# GALI.net
KiCad netlist of a schematic drawn in EAGLE
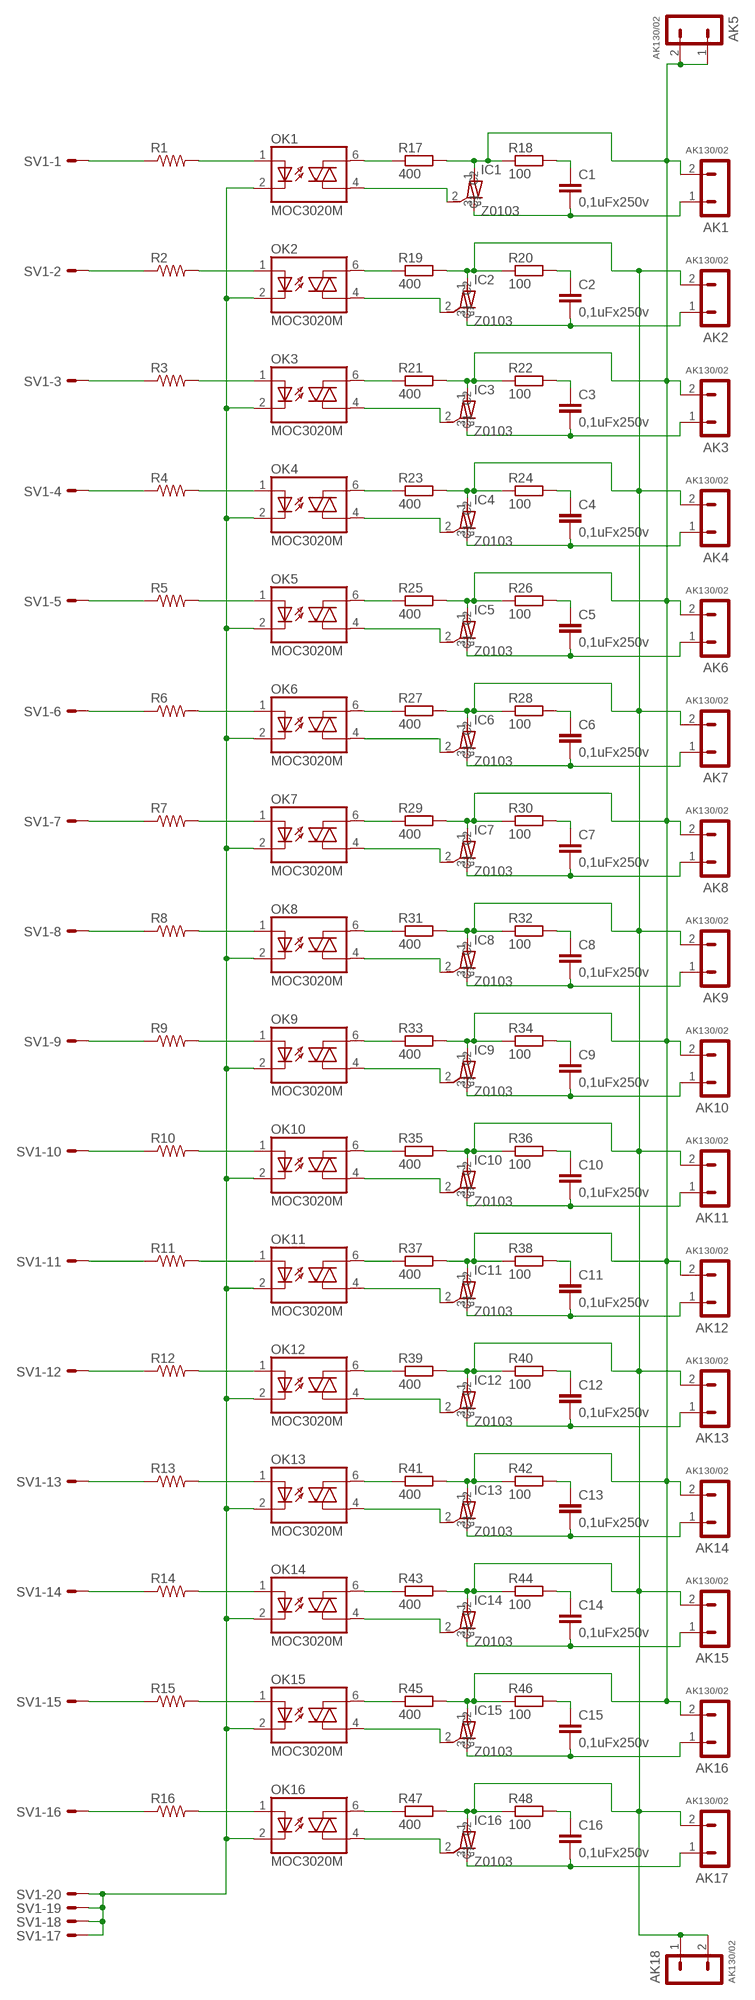
[diagram p0: schematic, sheet 1]

(export (version "E")
  (design (tool "Eeschema 10.0.6"))
  (components
    (comp (ref "AK1")
      (value "AK130/02")
      (footprint "eagle-import:AK02")
      (libsource (lib "eagle-import") (part "AK130/02"))
    )
    (comp (ref "AK2")
      (value "AK130/02")
      (footprint "eagle-import:AK02")
      (libsource (lib "eagle-import") (part "AK130/02"))
    )
    (comp (ref "AK3")
      (value "AK130/02")
      (footprint "eagle-import:AK02")
      (libsource (lib "eagle-import") (part "AK130/02"))
    )
    (comp (ref "AK4")
      (value "AK130/02")
      (footprint "eagle-import:AK02")
      (libsource (lib "eagle-import") (part "AK130/02"))
    )
    (comp (ref "AK5")
      (value "AK130/02")
      (footprint "eagle-import:AK02")
      (libsource (lib "eagle-import") (part "AK130/02"))
    )
    (comp (ref "AK6")
      (value "AK130/02")
      (footprint "eagle-import:AK02")
      (libsource (lib "eagle-import") (part "AK130/02"))
    )
    (comp (ref "AK7")
      (value "AK130/02")
      (footprint "eagle-import:AK02")
      (libsource (lib "eagle-import") (part "AK130/02"))
    )
    (comp (ref "AK8")
      (value "AK130/02")
      (footprint "eagle-import:AK02")
      (libsource (lib "eagle-import") (part "AK130/02"))
    )
    (comp (ref "AK9")
      (value "AK130/02")
      (footprint "eagle-import:AK02")
      (libsource (lib "eagle-import") (part "AK130/02"))
    )
    (comp (ref "AK10")
      (value "AK130/02")
      (footprint "eagle-import:AK02")
      (libsource (lib "eagle-import") (part "AK130/02"))
    )
    (comp (ref "AK11")
      (value "AK130/02")
      (footprint "eagle-import:AK02")
      (libsource (lib "eagle-import") (part "AK130/02"))
    )
    (comp (ref "AK12")
      (value "AK130/02")
      (footprint "eagle-import:AK02")
      (libsource (lib "eagle-import") (part "AK130/02"))
    )
    (comp (ref "AK13")
      (value "AK130/02")
      (footprint "eagle-import:AK02")
      (libsource (lib "eagle-import") (part "AK130/02"))
    )
    (comp (ref "AK14")
      (value "AK130/02")
      (footprint "eagle-import:AK02")
      (libsource (lib "eagle-import") (part "AK130/02"))
    )
    (comp (ref "AK15")
      (value "AK130/02")
      (footprint "eagle-import:AK02")
      (libsource (lib "eagle-import") (part "AK130/02"))
    )
    (comp (ref "AK16")
      (value "AK130/02")
      (footprint "eagle-import:AK02")
      (libsource (lib "eagle-import") (part "AK130/02"))
    )
    (comp (ref "AK17")
      (value "AK130/02")
      (footprint "eagle-import:AK02")
      (libsource (lib "eagle-import") (part "AK130/02"))
    )
    (comp (ref "AK18")
      (value "AK130/02")
      (footprint "eagle-import:AK02")
      (libsource (lib "eagle-import") (part "AK130/02"))
    )
    (comp (ref "C1")
      (value "0,1uFx250v")
      (footprint "eagle-import:C102-054X133")
      (libsource (lib "eagle-import") (part "C-EU102-054X133"))
    )
    (comp (ref "C2")
      (value "0,1uFx250v")
      (footprint "eagle-import:C102-054X133")
      (libsource (lib "eagle-import") (part "C-EU102-054X133"))
    )
    (comp (ref "C3")
      (value "0,1uFx250v")
      (footprint "eagle-import:C102-054X133")
      (libsource (lib "eagle-import") (part "C-EU102-054X133"))
    )
    (comp (ref "C4")
      (value "0,1uFx250v")
      (footprint "eagle-import:C102-054X133")
      (libsource (lib "eagle-import") (part "C-EU102-054X133"))
    )
    (comp (ref "C5")
      (value "0,1uFx250v")
      (footprint "eagle-import:C102-054X133")
      (libsource (lib "eagle-import") (part "C-EU102-054X133"))
    )
    (comp (ref "C6")
      (value "0,1uFx250v")
      (footprint "eagle-import:C102-054X133")
      (libsource (lib "eagle-import") (part "C-EU102-054X133"))
    )
    (comp (ref "C7")
      (value "0,1uFx250v")
      (footprint "eagle-import:C102-054X133")
      (libsource (lib "eagle-import") (part "C-EU102-054X133"))
    )
    (comp (ref "C8")
      (value "0,1uFx250v")
      (footprint "eagle-import:C102-054X133")
      (libsource (lib "eagle-import") (part "C-EU102-054X133"))
    )
    (comp (ref "C9")
      (value "0,1uFx250v")
      (footprint "eagle-import:C102-054X133")
      (libsource (lib "eagle-import") (part "C-EU102-054X133"))
    )
    (comp (ref "C10")
      (value "0,1uFx250v")
      (footprint "eagle-import:C102-054X133")
      (libsource (lib "eagle-import") (part "C-EU102-054X133"))
    )
    (comp (ref "C11")
      (value "0,1uFx250v")
      (footprint "eagle-import:C102-054X133")
      (libsource (lib "eagle-import") (part "C-EU102-054X133"))
    )
    (comp (ref "C12")
      (value "0,1uFx250v")
      (footprint "eagle-import:C102-054X133")
      (libsource (lib "eagle-import") (part "C-EU102-054X133"))
    )
    (comp (ref "C13")
      (value "0,1uFx250v")
      (footprint "eagle-import:C102-054X133")
      (libsource (lib "eagle-import") (part "C-EU102-054X133"))
    )
    (comp (ref "C14")
      (value "0,1uFx250v")
      (footprint "eagle-import:C102-054X133")
      (libsource (lib "eagle-import") (part "C-EU102-054X133"))
    )
    (comp (ref "C15")
      (value "0,1uFx250v")
      (footprint "eagle-import:C102-054X133")
      (libsource (lib "eagle-import") (part "C-EU102-054X133"))
    )
    (comp (ref "C16")
      (value "0,1uFx250v")
      (footprint "eagle-import:C102-054X133")
      (libsource (lib "eagle-import") (part "C-EU102-054X133"))
    )
    (comp (ref "IC1")
      (value "Z0103")
      (footprint "eagle-import:TO92-")
      (libsource (lib "eagle-import") (part "Z0103"))
    )
    (comp (ref "IC2")
      (value "Z0103")
      (footprint "eagle-import:TO92-")
      (libsource (lib "eagle-import") (part "Z0103"))
    )
    (comp (ref "IC3")
      (value "Z0103")
      (footprint "eagle-import:TO92-")
      (libsource (lib "eagle-import") (part "Z0103"))
    )
    (comp (ref "IC4")
      (value "Z0103")
      (footprint "eagle-import:TO92-")
      (libsource (lib "eagle-import") (part "Z0103"))
    )
    (comp (ref "IC5")
      (value "Z0103")
      (footprint "eagle-import:TO92-")
      (libsource (lib "eagle-import") (part "Z0103"))
    )
    (comp (ref "IC6")
      (value "Z0103")
      (footprint "eagle-import:TO92-")
      (libsource (lib "eagle-import") (part "Z0103"))
    )
    (comp (ref "IC7")
      (value "Z0103")
      (footprint "eagle-import:TO92-")
      (libsource (lib "eagle-import") (part "Z0103"))
    )
    (comp (ref "IC8")
      (value "Z0103")
      (footprint "eagle-import:TO92-")
      (libsource (lib "eagle-import") (part "Z0103"))
    )
    (comp (ref "IC9")
      (value "Z0103")
      (footprint "eagle-import:TO92-")
      (libsource (lib "eagle-import") (part "Z0103"))
    )
    (comp (ref "IC10")
      (value "Z0103")
      (footprint "eagle-import:TO92-")
      (libsource (lib "eagle-import") (part "Z0103"))
    )
    (comp (ref "IC11")
      (value "Z0103")
      (footprint "eagle-import:TO92-")
      (libsource (lib "eagle-import") (part "Z0103"))
    )
    (comp (ref "IC12")
      (value "Z0103")
      (footprint "eagle-import:TO92-")
      (libsource (lib "eagle-import") (part "Z0103"))
    )
    (comp (ref "IC13")
      (value "Z0103")
      (footprint "eagle-import:TO92-")
      (libsource (lib "eagle-import") (part "Z0103"))
    )
    (comp (ref "IC14")
      (value "Z0103")
      (footprint "eagle-import:TO92-")
      (libsource (lib "eagle-import") (part "Z0103"))
    )
    (comp (ref "IC15")
      (value "Z0103")
      (footprint "eagle-import:TO92-")
      (libsource (lib "eagle-import") (part "Z0103"))
    )
    (comp (ref "IC16")
      (value "Z0103")
      (footprint "eagle-import:TO92-")
      (libsource (lib "eagle-import") (part "Z0103"))
    )
    (comp (ref "OK1")
      (value "MOC3020M")
      (footprint "eagle-import:DIL06")
      (libsource (lib "eagle-import") (part "MOC30M20"))
    )
    (comp (ref "OK2")
      (value "MOC3020M")
      (footprint "eagle-import:DIL06")
      (libsource (lib "eagle-import") (part "MOC30M20"))
    )
    (comp (ref "OK3")
      (value "MOC3020M")
      (footprint "eagle-import:DIL06")
      (libsource (lib "eagle-import") (part "MOC30M20"))
    )
    (comp (ref "OK4")
      (value "MOC3020M")
      (footprint "eagle-import:DIL06")
      (libsource (lib "eagle-import") (part "MOC30M20"))
    )
    (comp (ref "OK5")
      (value "MOC3020M")
      (footprint "eagle-import:DIL06")
      (libsource (lib "eagle-import") (part "MOC30M20"))
    )
    (comp (ref "OK6")
      (value "MOC3020M")
      (footprint "eagle-import:DIL06")
      (libsource (lib "eagle-import") (part "MOC30M20"))
    )
    (comp (ref "OK7")
      (value "MOC3020M")
      (footprint "eagle-import:DIL06")
      (libsource (lib "eagle-import") (part "MOC30M20"))
    )
    (comp (ref "OK8")
      (value "MOC3020M")
      (footprint "eagle-import:DIL06")
      (libsource (lib "eagle-import") (part "MOC30M20"))
    )
    (comp (ref "OK9")
      (value "MOC3020M")
      (footprint "eagle-import:DIL06")
      (libsource (lib "eagle-import") (part "MOC30M20"))
    )
    (comp (ref "OK10")
      (value "MOC3020M")
      (footprint "eagle-import:DIL06")
      (libsource (lib "eagle-import") (part "MOC30M20"))
    )
    (comp (ref "OK11")
      (value "MOC3020M")
      (footprint "eagle-import:DIL06")
      (libsource (lib "eagle-import") (part "MOC30M20"))
    )
    (comp (ref "OK12")
      (value "MOC3020M")
      (footprint "eagle-import:DIL06")
      (libsource (lib "eagle-import") (part "MOC30M20"))
    )
    (comp (ref "OK13")
      (value "MOC3020M")
      (footprint "eagle-import:DIL06")
      (libsource (lib "eagle-import") (part "MOC30M20"))
    )
    (comp (ref "OK14")
      (value "MOC3020M")
      (footprint "eagle-import:DIL06")
      (libsource (lib "eagle-import") (part "MOC30M20"))
    )
    (comp (ref "OK15")
      (value "MOC3020M")
      (footprint "eagle-import:DIL06")
      (libsource (lib "eagle-import") (part "MOC30M20"))
    )
    (comp (ref "OK16")
      (value "MOC3020M")
      (footprint "eagle-import:DIL06")
      (libsource (lib "eagle-import") (part "MOC30M20"))
    )
    (comp (ref "R1")
      (value "R-US_0207/12")
      (footprint "eagle-import:0207_12")
      (libsource (lib "eagle-import") (part "R-US_0207/12"))
    )
    (comp (ref "R2")
      (value "R-US_0207/12")
      (footprint "eagle-import:0207_12")
      (libsource (lib "eagle-import") (part "R-US_0207/12"))
    )
    (comp (ref "R3")
      (value "R-US_0207/12")
      (footprint "eagle-import:0207_12")
      (libsource (lib "eagle-import") (part "R-US_0207/12"))
    )
    (comp (ref "R4")
      (value "R-US_0207/12")
      (footprint "eagle-import:0207_12")
      (libsource (lib "eagle-import") (part "R-US_0207/12"))
    )
    (comp (ref "R5")
      (value "R-US_0207/12")
      (footprint "eagle-import:0207_12")
      (libsource (lib "eagle-import") (part "R-US_0207/12"))
    )
    (comp (ref "R6")
      (value "R-US_0207/12")
      (footprint "eagle-import:0207_12")
      (libsource (lib "eagle-import") (part "R-US_0207/12"))
    )
    (comp (ref "R7")
      (value "R-US_0207/12")
      (footprint "eagle-import:0207_12")
      (libsource (lib "eagle-import") (part "R-US_0207/12"))
    )
    (comp (ref "R8")
      (value "R-US_0207/12")
      (footprint "eagle-import:0207_12")
      (libsource (lib "eagle-import") (part "R-US_0207/12"))
    )
    (comp (ref "R9")
      (value "R-US_0207/12")
      (footprint "eagle-import:0207_12")
      (libsource (lib "eagle-import") (part "R-US_0207/12"))
    )
    (comp (ref "R10")
      (value "R-US_0207/12")
      (footprint "eagle-import:0207_12")
      (libsource (lib "eagle-import") (part "R-US_0207/12"))
    )
    (comp (ref "R11")
      (value "R-US_0207/12")
      (footprint "eagle-import:0207_12")
      (libsource (lib "eagle-import") (part "R-US_0207/12"))
    )
    (comp (ref "R12")
      (value "R-US_0207/12")
      (footprint "eagle-import:0207_12")
      (libsource (lib "eagle-import") (part "R-US_0207/12"))
    )
    (comp (ref "R13")
      (value "R-US_0207/12")
      (footprint "eagle-import:0207_12")
      (libsource (lib "eagle-import") (part "R-US_0207/12"))
    )
    (comp (ref "R14")
      (value "R-US_0207/12")
      (footprint "eagle-import:0207_12")
      (libsource (lib "eagle-import") (part "R-US_0207/12"))
    )
    (comp (ref "R15")
      (value "R-US_0207/12")
      (footprint "eagle-import:0207_12")
      (libsource (lib "eagle-import") (part "R-US_0207/12"))
    )
    (comp (ref "R16")
      (value "R-US_0207/12")
      (footprint "eagle-import:0207_12")
      (libsource (lib "eagle-import") (part "R-US_0207/12"))
    )
    (comp (ref "R17")
      (value "400")
      (footprint "eagle-import:P0613_15")
      (libsource (lib "eagle-import") (part "R-EU_0613/15"))
    )
    (comp (ref "R18")
      (value "100")
      (footprint "eagle-import:P0613_15")
      (libsource (lib "eagle-import") (part "R-EU_0613/15"))
    )
    (comp (ref "R19")
      (value "400")
      (footprint "eagle-import:P0613_15")
      (libsource (lib "eagle-import") (part "R-EU_0613/15"))
    )
    (comp (ref "R20")
      (value "100")
      (footprint "eagle-import:P0613_15")
      (libsource (lib "eagle-import") (part "R-EU_0613/15"))
    )
    (comp (ref "R21")
      (value "400")
      (footprint "eagle-import:P0613_15")
      (libsource (lib "eagle-import") (part "R-EU_0613/15"))
    )
    (comp (ref "R22")
      (value "100")
      (footprint "eagle-import:P0613_15")
      (libsource (lib "eagle-import") (part "R-EU_0613/15"))
    )
    (comp (ref "R23")
      (value "400")
      (footprint "eagle-import:P0613_15")
      (libsource (lib "eagle-import") (part "R-EU_0613/15"))
    )
    (comp (ref "R24")
      (value "100")
      (footprint "eagle-import:P0613_15")
      (libsource (lib "eagle-import") (part "R-EU_0613/15"))
    )
    (comp (ref "R25")
      (value "400")
      (footprint "eagle-import:P0613_15")
      (libsource (lib "eagle-import") (part "R-EU_0613/15"))
    )
    (comp (ref "R26")
      (value "100")
      (footprint "eagle-import:P0613_15")
      (libsource (lib "eagle-import") (part "R-EU_0613/15"))
    )
    (comp (ref "R27")
      (value "400")
      (footprint "eagle-import:P0613_15")
      (libsource (lib "eagle-import") (part "R-EU_0613/15"))
    )
    (comp (ref "R28")
      (value "100")
      (footprint "eagle-import:P0613_15")
      (libsource (lib "eagle-import") (part "R-EU_0613/15"))
    )
    (comp (ref "R29")
      (value "400")
      (footprint "eagle-import:P0613_15")
      (libsource (lib "eagle-import") (part "R-EU_0613/15"))
    )
    (comp (ref "R30")
      (value "100")
      (footprint "eagle-import:P0613_15")
      (libsource (lib "eagle-import") (part "R-EU_0613/15"))
    )
    (comp (ref "R31")
      (value "400")
      (footprint "eagle-import:P0613_15")
      (libsource (lib "eagle-import") (part "R-EU_0613/15"))
    )
    (comp (ref "R32")
      (value "100")
      (footprint "eagle-import:P0613_15")
      (libsource (lib "eagle-import") (part "R-EU_0613/15"))
    )
    (comp (ref "R33")
      (value "400")
      (footprint "eagle-import:P0613_15")
      (libsource (lib "eagle-import") (part "R-EU_0613/15"))
    )
    (comp (ref "R34")
      (value "100")
      (footprint "eagle-import:P0613_15")
      (libsource (lib "eagle-import") (part "R-EU_0613/15"))
    )
    (comp (ref "R35")
      (value "400")
      (footprint "eagle-import:P0613_15")
      (libsource (lib "eagle-import") (part "R-EU_0613/15"))
    )
    (comp (ref "R36")
      (value "100")
      (footprint "eagle-import:P0613_15")
      (libsource (lib "eagle-import") (part "R-EU_0613/15"))
    )
    (comp (ref "R37")
      (value "400")
      (footprint "eagle-import:P0613_15")
      (libsource (lib "eagle-import") (part "R-EU_0613/15"))
    )
    (comp (ref "R38")
      (value "100")
      (footprint "eagle-import:P0613_15")
      (libsource (lib "eagle-import") (part "R-EU_0613/15"))
    )
    (comp (ref "R39")
      (value "400")
      (footprint "eagle-import:P0613_15")
      (libsource (lib "eagle-import") (part "R-EU_0613/15"))
    )
    (comp (ref "R40")
      (value "100")
      (footprint "eagle-import:P0613_15")
      (libsource (lib "eagle-import") (part "R-EU_0613/15"))
    )
    (comp (ref "R41")
      (value "400")
      (footprint "eagle-import:P0613_15")
      (libsource (lib "eagle-import") (part "R-EU_0613/15"))
    )
    (comp (ref "R42")
      (value "100")
      (footprint "eagle-import:P0613_15")
      (libsource (lib "eagle-import") (part "R-EU_0613/15"))
    )
    (comp (ref "R43")
      (value "400")
      (footprint "eagle-import:P0613_15")
      (libsource (lib "eagle-import") (part "R-EU_0613/15"))
    )
    (comp (ref "R44")
      (value "100")
      (footprint "eagle-import:P0613_15")
      (libsource (lib "eagle-import") (part "R-EU_0613/15"))
    )
    (comp (ref "R45")
      (value "400")
      (footprint "eagle-import:P0613_15")
      (libsource (lib "eagle-import") (part "R-EU_0613/15"))
    )
    (comp (ref "R46")
      (value "100")
      (footprint "eagle-import:P0613_15")
      (libsource (lib "eagle-import") (part "R-EU_0613/15"))
    )
    (comp (ref "R47")
      (value "400")
      (footprint "eagle-import:P0613_15")
      (libsource (lib "eagle-import") (part "R-EU_0613/15"))
    )
    (comp (ref "R48")
      (value "100")
      (footprint "eagle-import:P0613_15")
      (libsource (lib "eagle-import") (part "R-EU_0613/15"))
    )
    (comp (ref "SV1")
      (value "ML20E")
      (footprint "eagle-import:ML20")
      (libsource (lib "eagle-import") (part "ML20?E"))
    )
  )
  (nets
    (net (code "1") (name "Net-(AK1-P$1)") (class "Default")
      (node (ref "AK1") (pin "1") (pinfunction "P$1_1") (pintype "bidirectional"))
      (node (ref "C1") (pin "2") (pinfunction "2_2") (pintype "passive"))
      (node (ref "IC1") (pin "3") (pinfunction "C2_3") (pintype "passive"))
    )
    (net (code "2") (name "Net-(AK1-P$2)") (class "Default")
      (node (ref "AK1") (pin "2") (pinfunction "P$2_2") (pintype "bidirectional"))
      (node (ref "AK10") (pin "2") (pinfunction "P$2_2") (pintype "bidirectional"))
      (node (ref "AK12") (pin "2") (pinfunction "P$2_2") (pintype "bidirectional"))
      (node (ref "AK14") (pin "2") (pinfunction "P$2_2") (pintype "bidirectional"))
      (node (ref "AK16") (pin "2") (pinfunction "P$2_2") (pintype "bidirectional"))
      (node (ref "AK3") (pin "2") (pinfunction "P$2_2") (pintype "bidirectional"))
      (node (ref "AK5") (pin "1") (pinfunction "P$1_1") (pintype "bidirectional"))
      (node (ref "AK5") (pin "2") (pinfunction "P$2_2") (pintype "bidirectional"))
      (node (ref "AK6") (pin "2") (pinfunction "P$2_2") (pintype "bidirectional"))
      (node (ref "AK8") (pin "2") (pinfunction "P$2_2") (pintype "bidirectional"))
      (node (ref "IC1") (pin "1") (pinfunction "C1_1") (pintype "passive"))
      (node (ref "IC11") (pin "1") (pinfunction "C1_1") (pintype "passive"))
      (node (ref "IC13") (pin "1") (pinfunction "C1_1") (pintype "passive"))
      (node (ref "IC15") (pin "1") (pinfunction "C1_1") (pintype "passive"))
      (node (ref "IC3") (pin "1") (pinfunction "C1_1") (pintype "passive"))
      (node (ref "IC5") (pin "1") (pinfunction "C1_1") (pintype "passive"))
      (node (ref "IC7") (pin "1") (pinfunction "C1_1") (pintype "passive"))
      (node (ref "IC9") (pin "1") (pinfunction "C1_1") (pintype "passive"))
      (node (ref "R17") (pin "2") (pinfunction "2_2") (pintype "passive"))
      (node (ref "R18") (pin "1") (pinfunction "1_1") (pintype "passive"))
      (node (ref "R21") (pin "2") (pinfunction "2_2") (pintype "passive"))
      (node (ref "R22") (pin "1") (pinfunction "1_1") (pintype "passive"))
      (node (ref "R25") (pin "2") (pinfunction "2_2") (pintype "passive"))
      (node (ref "R26") (pin "1") (pinfunction "1_1") (pintype "passive"))
      (node (ref "R29") (pin "2") (pinfunction "2_2") (pintype "passive"))
      (node (ref "R30") (pin "1") (pinfunction "1_1") (pintype "passive"))
      (node (ref "R33") (pin "2") (pinfunction "2_2") (pintype "passive"))
      (node (ref "R34") (pin "1") (pinfunction "1_1") (pintype "passive"))
      (node (ref "R37") (pin "2") (pinfunction "2_2") (pintype "passive"))
      (node (ref "R38") (pin "1") (pinfunction "1_1") (pintype "passive"))
      (node (ref "R41") (pin "2") (pinfunction "2_2") (pintype "passive"))
      (node (ref "R42") (pin "1") (pinfunction "1_1") (pintype "passive"))
      (node (ref "R45") (pin "2") (pinfunction "2_2") (pintype "passive"))
      (node (ref "R46") (pin "1") (pinfunction "1_1") (pintype "passive"))
    )
    (net (code "3") (name "Net-(AK2-P$1)") (class "Default")
      (node (ref "AK2") (pin "1") (pinfunction "P$1_1") (pintype "bidirectional"))
      (node (ref "C2") (pin "2") (pinfunction "2_2") (pintype "passive"))
      (node (ref "IC2") (pin "3") (pinfunction "C2_3") (pintype "passive"))
    )
    (net (code "4") (name "Net-(AK3-P$1)") (class "Default")
      (node (ref "AK3") (pin "1") (pinfunction "P$1_1") (pintype "bidirectional"))
      (node (ref "C3") (pin "2") (pinfunction "2_2") (pintype "passive"))
      (node (ref "IC3") (pin "3") (pinfunction "C2_3") (pintype "passive"))
    )
    (net (code "5") (name "Net-(AK4-P$1)") (class "Default")
      (node (ref "AK4") (pin "1") (pinfunction "P$1_1") (pintype "bidirectional"))
      (node (ref "C4") (pin "2") (pinfunction "2_2") (pintype "passive"))
      (node (ref "IC4") (pin "3") (pinfunction "C2_3") (pintype "passive"))
    )
    (net (code "6") (name "Net-(AK6-P$1)") (class "Default")
      (node (ref "AK6") (pin "1") (pinfunction "P$1_1") (pintype "bidirectional"))
      (node (ref "C5") (pin "2") (pinfunction "2_2") (pintype "passive"))
      (node (ref "IC5") (pin "3") (pinfunction "C2_3") (pintype "passive"))
    )
    (net (code "7") (name "Net-(AK7-P$1)") (class "Default")
      (node (ref "AK7") (pin "1") (pinfunction "P$1_1") (pintype "bidirectional"))
      (node (ref "C6") (pin "2") (pinfunction "2_2") (pintype "passive"))
      (node (ref "IC6") (pin "3") (pinfunction "C2_3") (pintype "passive"))
    )
    (net (code "8") (name "Net-(AK8-P$1)") (class "Default")
      (node (ref "AK8") (pin "1") (pinfunction "P$1_1") (pintype "bidirectional"))
      (node (ref "C7") (pin "2") (pinfunction "2_2") (pintype "passive"))
      (node (ref "IC7") (pin "3") (pinfunction "C2_3") (pintype "passive"))
    )
    (net (code "9") (name "Net-(AK9-P$1)") (class "Default")
      (node (ref "AK9") (pin "1") (pinfunction "P$1_1") (pintype "bidirectional"))
      (node (ref "C8") (pin "2") (pinfunction "2_2") (pintype "passive"))
      (node (ref "IC8") (pin "3") (pinfunction "C2_3") (pintype "passive"))
    )
    (net (code "10") (name "Net-(AK10-P$1)") (class "Default")
      (node (ref "AK10") (pin "1") (pinfunction "P$1_1") (pintype "bidirectional"))
      (node (ref "C9") (pin "2") (pinfunction "2_2") (pintype "passive"))
      (node (ref "IC9") (pin "3") (pinfunction "C2_3") (pintype "passive"))
    )
    (net (code "11") (name "Net-(AK11-P$1)") (class "Default")
      (node (ref "AK11") (pin "1") (pinfunction "P$1_1") (pintype "bidirectional"))
      (node (ref "C10") (pin "2") (pinfunction "2_2") (pintype "passive"))
      (node (ref "IC10") (pin "3") (pinfunction "C2_3") (pintype "passive"))
    )
    (net (code "12") (name "Net-(AK11-P$2)") (class "Default")
      (node (ref "AK11") (pin "2") (pinfunction "P$2_2") (pintype "bidirectional"))
      (node (ref "AK13") (pin "2") (pinfunction "P$2_2") (pintype "bidirectional"))
      (node (ref "AK15") (pin "2") (pinfunction "P$2_2") (pintype "bidirectional"))
      (node (ref "AK17") (pin "2") (pinfunction "P$2_2") (pintype "bidirectional"))
      (node (ref "AK18") (pin "1") (pinfunction "P$1_1") (pintype "bidirectional"))
      (node (ref "AK18") (pin "2") (pinfunction "P$2_2") (pintype "bidirectional"))
      (node (ref "AK2") (pin "2") (pinfunction "P$2_2") (pintype "bidirectional"))
      (node (ref "AK4") (pin "2") (pinfunction "P$2_2") (pintype "bidirectional"))
      (node (ref "AK7") (pin "2") (pinfunction "P$2_2") (pintype "bidirectional"))
      (node (ref "AK9") (pin "2") (pinfunction "P$2_2") (pintype "bidirectional"))
      (node (ref "IC10") (pin "1") (pinfunction "C1_1") (pintype "passive"))
      (node (ref "IC12") (pin "1") (pinfunction "C1_1") (pintype "passive"))
      (node (ref "IC14") (pin "1") (pinfunction "C1_1") (pintype "passive"))
      (node (ref "IC16") (pin "1") (pinfunction "C1_1") (pintype "passive"))
      (node (ref "IC2") (pin "1") (pinfunction "C1_1") (pintype "passive"))
      (node (ref "IC4") (pin "1") (pinfunction "C1_1") (pintype "passive"))
      (node (ref "IC6") (pin "1") (pinfunction "C1_1") (pintype "passive"))
      (node (ref "IC8") (pin "1") (pinfunction "C1_1") (pintype "passive"))
      (node (ref "R19") (pin "2") (pinfunction "2_2") (pintype "passive"))
      (node (ref "R20") (pin "1") (pinfunction "1_1") (pintype "passive"))
      (node (ref "R23") (pin "2") (pinfunction "2_2") (pintype "passive"))
      (node (ref "R24") (pin "1") (pinfunction "1_1") (pintype "passive"))
      (node (ref "R27") (pin "2") (pinfunction "2_2") (pintype "passive"))
      (node (ref "R28") (pin "1") (pinfunction "1_1") (pintype "passive"))
      (node (ref "R31") (pin "2") (pinfunction "2_2") (pintype "passive"))
      (node (ref "R32") (pin "1") (pinfunction "1_1") (pintype "passive"))
      (node (ref "R35") (pin "2") (pinfunction "2_2") (pintype "passive"))
      (node (ref "R36") (pin "1") (pinfunction "1_1") (pintype "passive"))
      (node (ref "R39") (pin "2") (pinfunction "2_2") (pintype "passive"))
      (node (ref "R40") (pin "1") (pinfunction "1_1") (pintype "passive"))
      (node (ref "R43") (pin "2") (pinfunction "2_2") (pintype "passive"))
      (node (ref "R44") (pin "1") (pinfunction "1_1") (pintype "passive"))
      (node (ref "R47") (pin "2") (pinfunction "2_2") (pintype "passive"))
      (node (ref "R48") (pin "1") (pinfunction "1_1") (pintype "passive"))
    )
    (net (code "13") (name "Net-(AK12-P$1)") (class "Default")
      (node (ref "AK12") (pin "1") (pinfunction "P$1_1") (pintype "bidirectional"))
      (node (ref "C11") (pin "2") (pinfunction "2_2") (pintype "passive"))
      (node (ref "IC11") (pin "3") (pinfunction "C2_3") (pintype "passive"))
    )
    (net (code "14") (name "Net-(AK13-P$1)") (class "Default")
      (node (ref "AK13") (pin "1") (pinfunction "P$1_1") (pintype "bidirectional"))
      (node (ref "C12") (pin "2") (pinfunction "2_2") (pintype "passive"))
      (node (ref "IC12") (pin "3") (pinfunction "C2_3") (pintype "passive"))
    )
    (net (code "15") (name "Net-(AK14-P$1)") (class "Default")
      (node (ref "AK14") (pin "1") (pinfunction "P$1_1") (pintype "bidirectional"))
      (node (ref "C13") (pin "2") (pinfunction "2_2") (pintype "passive"))
      (node (ref "IC13") (pin "3") (pinfunction "C2_3") (pintype "passive"))
    )
    (net (code "16") (name "Net-(AK15-P$1)") (class "Default")
      (node (ref "AK15") (pin "1") (pinfunction "P$1_1") (pintype "bidirectional"))
      (node (ref "C14") (pin "2") (pinfunction "2_2") (pintype "passive"))
      (node (ref "IC14") (pin "3") (pinfunction "C2_3") (pintype "passive"))
    )
    (net (code "17") (name "Net-(AK16-P$1)") (class "Default")
      (node (ref "AK16") (pin "1") (pinfunction "P$1_1") (pintype "bidirectional"))
      (node (ref "C15") (pin "2") (pinfunction "2_2") (pintype "passive"))
      (node (ref "IC15") (pin "3") (pinfunction "C2_3") (pintype "passive"))
    )
    (net (code "18") (name "Net-(AK17-P$1)") (class "Default")
      (node (ref "AK17") (pin "1") (pinfunction "P$1_1") (pintype "bidirectional"))
      (node (ref "C16") (pin "2") (pinfunction "2_2") (pintype "passive"))
      (node (ref "IC16") (pin "3") (pinfunction "C2_3") (pintype "passive"))
    )
    (net (code "19") (name "Net-(C1-Pad1)") (class "Default")
      (node (ref "C1") (pin "1") (pinfunction "1_1") (pintype "passive"))
      (node (ref "R18") (pin "2") (pinfunction "2_2") (pintype "passive"))
    )
    (net (code "20") (name "Net-(C2-Pad1)") (class "Default")
      (node (ref "C2") (pin "1") (pinfunction "1_1") (pintype "passive"))
      (node (ref "R20") (pin "2") (pinfunction "2_2") (pintype "passive"))
    )
    (net (code "21") (name "Net-(C3-Pad1)") (class "Default")
      (node (ref "C3") (pin "1") (pinfunction "1_1") (pintype "passive"))
      (node (ref "R22") (pin "2") (pinfunction "2_2") (pintype "passive"))
    )
    (net (code "22") (name "Net-(C4-Pad1)") (class "Default")
      (node (ref "C4") (pin "1") (pinfunction "1_1") (pintype "passive"))
      (node (ref "R24") (pin "2") (pinfunction "2_2") (pintype "passive"))
    )
    (net (code "23") (name "Net-(C5-Pad1)") (class "Default")
      (node (ref "C5") (pin "1") (pinfunction "1_1") (pintype "passive"))
      (node (ref "R26") (pin "2") (pinfunction "2_2") (pintype "passive"))
    )
    (net (code "24") (name "Net-(C6-Pad1)") (class "Default")
      (node (ref "C6") (pin "1") (pinfunction "1_1") (pintype "passive"))
      (node (ref "R28") (pin "2") (pinfunction "2_2") (pintype "passive"))
    )
    (net (code "25") (name "Net-(C7-Pad1)") (class "Default")
      (node (ref "C7") (pin "1") (pinfunction "1_1") (pintype "passive"))
      (node (ref "R30") (pin "2") (pinfunction "2_2") (pintype "passive"))
    )
    (net (code "26") (name "Net-(C8-Pad1)") (class "Default")
      (node (ref "C8") (pin "1") (pinfunction "1_1") (pintype "passive"))
      (node (ref "R32") (pin "2") (pinfunction "2_2") (pintype "passive"))
    )
    (net (code "27") (name "Net-(C9-Pad1)") (class "Default")
      (node (ref "C9") (pin "1") (pinfunction "1_1") (pintype "passive"))
      (node (ref "R34") (pin "2") (pinfunction "2_2") (pintype "passive"))
    )
    (net (code "28") (name "Net-(C10-Pad1)") (class "Default")
      (node (ref "C10") (pin "1") (pinfunction "1_1") (pintype "passive"))
      (node (ref "R36") (pin "2") (pinfunction "2_2") (pintype "passive"))
    )
    (net (code "29") (name "Net-(C11-Pad1)") (class "Default")
      (node (ref "C11") (pin "1") (pinfunction "1_1") (pintype "passive"))
      (node (ref "R38") (pin "2") (pinfunction "2_2") (pintype "passive"))
    )
    (net (code "30") (name "Net-(C12-Pad1)") (class "Default")
      (node (ref "C12") (pin "1") (pinfunction "1_1") (pintype "passive"))
      (node (ref "R40") (pin "2") (pinfunction "2_2") (pintype "passive"))
    )
    (net (code "31") (name "Net-(C13-Pad1)") (class "Default")
      (node (ref "C13") (pin "1") (pinfunction "1_1") (pintype "passive"))
      (node (ref "R42") (pin "2") (pinfunction "2_2") (pintype "passive"))
    )
    (net (code "32") (name "Net-(C14-Pad1)") (class "Default")
      (node (ref "C14") (pin "1") (pinfunction "1_1") (pintype "passive"))
      (node (ref "R44") (pin "2") (pinfunction "2_2") (pintype "passive"))
    )
    (net (code "33") (name "Net-(C15-Pad1)") (class "Default")
      (node (ref "C15") (pin "1") (pinfunction "1_1") (pintype "passive"))
      (node (ref "R46") (pin "2") (pinfunction "2_2") (pintype "passive"))
    )
    (net (code "34") (name "Net-(C16-Pad1)") (class "Default")
      (node (ref "C16") (pin "1") (pinfunction "1_1") (pintype "passive"))
      (node (ref "R48") (pin "2") (pinfunction "2_2") (pintype "passive"))
    )
    (net (code "35") (name "Net-(IC1-G)") (class "Default")
      (node (ref "IC1") (pin "2") (pinfunction "G_2") (pintype "passive"))
      (node (ref "OK1") (pin "4") (pinfunction "A1_4") (pintype "passive"))
    )
    (net (code "36") (name "Net-(IC2-G)") (class "Default")
      (node (ref "IC2") (pin "2") (pinfunction "G_2") (pintype "passive"))
      (node (ref "OK2") (pin "4") (pinfunction "A1_4") (pintype "passive"))
    )
    (net (code "37") (name "Net-(IC3-G)") (class "Default")
      (node (ref "IC3") (pin "2") (pinfunction "G_2") (pintype "passive"))
      (node (ref "OK3") (pin "4") (pinfunction "A1_4") (pintype "passive"))
    )
    (net (code "38") (name "Net-(IC4-G)") (class "Default")
      (node (ref "IC4") (pin "2") (pinfunction "G_2") (pintype "passive"))
      (node (ref "OK4") (pin "4") (pinfunction "A1_4") (pintype "passive"))
    )
    (net (code "39") (name "Net-(IC5-G)") (class "Default")
      (node (ref "IC5") (pin "2") (pinfunction "G_2") (pintype "passive"))
      (node (ref "OK5") (pin "4") (pinfunction "A1_4") (pintype "passive"))
    )
    (net (code "40") (name "Net-(IC6-G)") (class "Default")
      (node (ref "IC6") (pin "2") (pinfunction "G_2") (pintype "passive"))
      (node (ref "OK6") (pin "4") (pinfunction "A1_4") (pintype "passive"))
    )
    (net (code "41") (name "Net-(IC7-G)") (class "Default")
      (node (ref "IC7") (pin "2") (pinfunction "G_2") (pintype "passive"))
      (node (ref "OK7") (pin "4") (pinfunction "A1_4") (pintype "passive"))
    )
    (net (code "42") (name "Net-(IC8-G)") (class "Default")
      (node (ref "IC8") (pin "2") (pinfunction "G_2") (pintype "passive"))
      (node (ref "OK8") (pin "4") (pinfunction "A1_4") (pintype "passive"))
    )
    (net (code "43") (name "Net-(IC9-G)") (class "Default")
      (node (ref "IC9") (pin "2") (pinfunction "G_2") (pintype "passive"))
      (node (ref "OK9") (pin "4") (pinfunction "A1_4") (pintype "passive"))
    )
    (net (code "44") (name "Net-(IC10-G)") (class "Default")
      (node (ref "IC10") (pin "2") (pinfunction "G_2") (pintype "passive"))
      (node (ref "OK10") (pin "4") (pinfunction "A1_4") (pintype "passive"))
    )
    (net (code "45") (name "Net-(IC11-G)") (class "Default")
      (node (ref "IC11") (pin "2") (pinfunction "G_2") (pintype "passive"))
      (node (ref "OK11") (pin "4") (pinfunction "A1_4") (pintype "passive"))
    )
    (net (code "46") (name "Net-(IC12-G)") (class "Default")
      (node (ref "IC12") (pin "2") (pinfunction "G_2") (pintype "passive"))
      (node (ref "OK12") (pin "4") (pinfunction "A1_4") (pintype "passive"))
    )
    (net (code "47") (name "Net-(IC13-G)") (class "Default")
      (node (ref "IC13") (pin "2") (pinfunction "G_2") (pintype "passive"))
      (node (ref "OK13") (pin "4") (pinfunction "A1_4") (pintype "passive"))
    )
    (net (code "48") (name "Net-(IC14-G)") (class "Default")
      (node (ref "IC14") (pin "2") (pinfunction "G_2") (pintype "passive"))
      (node (ref "OK14") (pin "4") (pinfunction "A1_4") (pintype "passive"))
    )
    (net (code "49") (name "Net-(IC15-G)") (class "Default")
      (node (ref "IC15") (pin "2") (pinfunction "G_2") (pintype "passive"))
      (node (ref "OK15") (pin "4") (pinfunction "A1_4") (pintype "passive"))
    )
    (net (code "50") (name "Net-(IC16-G)") (class "Default")
      (node (ref "IC16") (pin "2") (pinfunction "G_2") (pintype "passive"))
      (node (ref "OK16") (pin "4") (pinfunction "A1_4") (pintype "passive"))
    )
    (net (code "51") (name "Net-(OK1-A)") (class "Default")
      (node (ref "OK1") (pin "1") (pinfunction "A_1") (pintype "passive"))
      (node (ref "R1") (pin "2") (pinfunction "2_2") (pintype "passive"))
    )
    (net (code "52") (name "Net-(OK1-A2)") (class "Default")
      (node (ref "OK1") (pin "6") (pinfunction "A2_6") (pintype "passive"))
      (node (ref "R17") (pin "1") (pinfunction "1_1") (pintype "passive"))
    )
    (net (code "53") (name "Net-(OK1-C)") (class "Default")
      (node (ref "OK1") (pin "2") (pinfunction "C_2") (pintype "passive"))
      (node (ref "OK10") (pin "2") (pinfunction "C_2") (pintype "passive"))
      (node (ref "OK11") (pin "2") (pinfunction "C_2") (pintype "passive"))
      (node (ref "OK12") (pin "2") (pinfunction "C_2") (pintype "passive"))
      (node (ref "OK13") (pin "2") (pinfunction "C_2") (pintype "passive"))
      (node (ref "OK14") (pin "2") (pinfunction "C_2") (pintype "passive"))
      (node (ref "OK15") (pin "2") (pinfunction "C_2") (pintype "passive"))
      (node (ref "OK16") (pin "2") (pinfunction "C_2") (pintype "passive"))
      (node (ref "OK2") (pin "2") (pinfunction "C_2") (pintype "passive"))
      (node (ref "OK3") (pin "2") (pinfunction "C_2") (pintype "passive"))
      (node (ref "OK4") (pin "2") (pinfunction "C_2") (pintype "passive"))
      (node (ref "OK5") (pin "2") (pinfunction "C_2") (pintype "passive"))
      (node (ref "OK6") (pin "2") (pinfunction "C_2") (pintype "passive"))
      (node (ref "OK7") (pin "2") (pinfunction "C_2") (pintype "passive"))
      (node (ref "OK8") (pin "2") (pinfunction "C_2") (pintype "passive"))
      (node (ref "OK9") (pin "2") (pinfunction "C_2") (pintype "passive"))
      (node (ref "SV1") (pin "17") (pinfunction "S_17") (pintype "passive"))
      (node (ref "SV1") (pin "18") (pinfunction "S_18") (pintype "passive"))
      (node (ref "SV1") (pin "19") (pinfunction "S_19") (pintype "passive"))
      (node (ref "SV1") (pin "20") (pinfunction "S_20") (pintype "passive"))
    )
    (net (code "54") (name "Net-(OK2-A)") (class "Default")
      (node (ref "OK2") (pin "1") (pinfunction "A_1") (pintype "passive"))
      (node (ref "R2") (pin "2") (pinfunction "2_2") (pintype "passive"))
    )
    (net (code "55") (name "Net-(OK2-A2)") (class "Default")
      (node (ref "OK2") (pin "6") (pinfunction "A2_6") (pintype "passive"))
      (node (ref "R19") (pin "1") (pinfunction "1_1") (pintype "passive"))
    )
    (net (code "56") (name "Net-(OK3-A)") (class "Default")
      (node (ref "OK3") (pin "1") (pinfunction "A_1") (pintype "passive"))
      (node (ref "R3") (pin "2") (pinfunction "2_2") (pintype "passive"))
    )
    (net (code "57") (name "Net-(OK3-A2)") (class "Default")
      (node (ref "OK3") (pin "6") (pinfunction "A2_6") (pintype "passive"))
      (node (ref "R21") (pin "1") (pinfunction "1_1") (pintype "passive"))
    )
    (net (code "58") (name "Net-(OK4-A)") (class "Default")
      (node (ref "OK4") (pin "1") (pinfunction "A_1") (pintype "passive"))
      (node (ref "R4") (pin "2") (pinfunction "2_2") (pintype "passive"))
    )
    (net (code "59") (name "Net-(OK4-A2)") (class "Default")
      (node (ref "OK4") (pin "6") (pinfunction "A2_6") (pintype "passive"))
      (node (ref "R23") (pin "1") (pinfunction "1_1") (pintype "passive"))
    )
    (net (code "60") (name "Net-(OK5-A)") (class "Default")
      (node (ref "OK5") (pin "1") (pinfunction "A_1") (pintype "passive"))
      (node (ref "R5") (pin "2") (pinfunction "2_2") (pintype "passive"))
    )
    (net (code "61") (name "Net-(OK5-A2)") (class "Default")
      (node (ref "OK5") (pin "6") (pinfunction "A2_6") (pintype "passive"))
      (node (ref "R25") (pin "1") (pinfunction "1_1") (pintype "passive"))
    )
    (net (code "62") (name "Net-(OK6-A)") (class "Default")
      (node (ref "OK6") (pin "1") (pinfunction "A_1") (pintype "passive"))
      (node (ref "R6") (pin "2") (pinfunction "2_2") (pintype "passive"))
    )
    (net (code "63") (name "Net-(OK6-A2)") (class "Default")
      (node (ref "OK6") (pin "6") (pinfunction "A2_6") (pintype "passive"))
      (node (ref "R27") (pin "1") (pinfunction "1_1") (pintype "passive"))
    )
    (net (code "64") (name "Net-(OK7-A)") (class "Default")
      (node (ref "OK7") (pin "1") (pinfunction "A_1") (pintype "passive"))
      (node (ref "R7") (pin "2") (pinfunction "2_2") (pintype "passive"))
    )
    (net (code "65") (name "Net-(OK7-A2)") (class "Default")
      (node (ref "OK7") (pin "6") (pinfunction "A2_6") (pintype "passive"))
      (node (ref "R29") (pin "1") (pinfunction "1_1") (pintype "passive"))
    )
    (net (code "66") (name "Net-(OK8-A)") (class "Default")
      (node (ref "OK8") (pin "1") (pinfunction "A_1") (pintype "passive"))
      (node (ref "R8") (pin "2") (pinfunction "2_2") (pintype "passive"))
    )
    (net (code "67") (name "Net-(OK8-A2)") (class "Default")
      (node (ref "OK8") (pin "6") (pinfunction "A2_6") (pintype "passive"))
      (node (ref "R31") (pin "1") (pinfunction "1_1") (pintype "passive"))
    )
    (net (code "68") (name "Net-(OK9-A)") (class "Default")
      (node (ref "OK9") (pin "1") (pinfunction "A_1") (pintype "passive"))
      (node (ref "R9") (pin "2") (pinfunction "2_2") (pintype "passive"))
    )
    (net (code "69") (name "Net-(OK9-A2)") (class "Default")
      (node (ref "OK9") (pin "6") (pinfunction "A2_6") (pintype "passive"))
      (node (ref "R33") (pin "1") (pinfunction "1_1") (pintype "passive"))
    )
    (net (code "70") (name "Net-(OK10-A)") (class "Default")
      (node (ref "OK10") (pin "1") (pinfunction "A_1") (pintype "passive"))
      (node (ref "R10") (pin "2") (pinfunction "2_2") (pintype "passive"))
    )
    (net (code "71") (name "Net-(OK10-A2)") (class "Default")
      (node (ref "OK10") (pin "6") (pinfunction "A2_6") (pintype "passive"))
      (node (ref "R35") (pin "1") (pinfunction "1_1") (pintype "passive"))
    )
    (net (code "72") (name "Net-(OK11-A)") (class "Default")
      (node (ref "OK11") (pin "1") (pinfunction "A_1") (pintype "passive"))
      (node (ref "R11") (pin "2") (pinfunction "2_2") (pintype "passive"))
    )
    (net (code "73") (name "Net-(OK11-A2)") (class "Default")
      (node (ref "OK11") (pin "6") (pinfunction "A2_6") (pintype "passive"))
      (node (ref "R37") (pin "1") (pinfunction "1_1") (pintype "passive"))
    )
    (net (code "74") (name "Net-(OK12-A)") (class "Default")
      (node (ref "OK12") (pin "1") (pinfunction "A_1") (pintype "passive"))
      (node (ref "R12") (pin "2") (pinfunction "2_2") (pintype "passive"))
    )
    (net (code "75") (name "Net-(OK12-A2)") (class "Default")
      (node (ref "OK12") (pin "6") (pinfunction "A2_6") (pintype "passive"))
      (node (ref "R39") (pin "1") (pinfunction "1_1") (pintype "passive"))
    )
    (net (code "76") (name "Net-(OK13-A)") (class "Default")
      (node (ref "OK13") (pin "1") (pinfunction "A_1") (pintype "passive"))
      (node (ref "R13") (pin "2") (pinfunction "2_2") (pintype "passive"))
    )
    (net (code "77") (name "Net-(OK13-A2)") (class "Default")
      (node (ref "OK13") (pin "6") (pinfunction "A2_6") (pintype "passive"))
      (node (ref "R41") (pin "1") (pinfunction "1_1") (pintype "passive"))
    )
    (net (code "78") (name "Net-(OK14-A)") (class "Default")
      (node (ref "OK14") (pin "1") (pinfunction "A_1") (pintype "passive"))
      (node (ref "R14") (pin "2") (pinfunction "2_2") (pintype "passive"))
    )
    (net (code "79") (name "Net-(OK14-A2)") (class "Default")
      (node (ref "OK14") (pin "6") (pinfunction "A2_6") (pintype "passive"))
      (node (ref "R43") (pin "1") (pinfunction "1_1") (pintype "passive"))
    )
    (net (code "80") (name "Net-(OK15-A)") (class "Default")
      (node (ref "OK15") (pin "1") (pinfunction "A_1") (pintype "passive"))
      (node (ref "R15") (pin "2") (pinfunction "2_2") (pintype "passive"))
    )
    (net (code "81") (name "Net-(OK15-A2)") (class "Default")
      (node (ref "OK15") (pin "6") (pinfunction "A2_6") (pintype "passive"))
      (node (ref "R45") (pin "1") (pinfunction "1_1") (pintype "passive"))
    )
    (net (code "82") (name "Net-(OK16-A)") (class "Default")
      (node (ref "OK16") (pin "1") (pinfunction "A_1") (pintype "passive"))
      (node (ref "R16") (pin "2") (pinfunction "2_2") (pintype "passive"))
    )
    (net (code "83") (name "Net-(OK16-A2)") (class "Default")
      (node (ref "OK16") (pin "6") (pinfunction "A2_6") (pintype "passive"))
      (node (ref "R47") (pin "1") (pinfunction "1_1") (pintype "passive"))
    )
    (net (code "84") (name "Net-(SV1A-S)") (class "Default")
      (node (ref "R1") (pin "1") (pinfunction "1_1") (pintype "passive"))
      (node (ref "SV1") (pin "1") (pinfunction "S_1") (pintype "passive"))
    )
    (net (code "85") (name "Net-(SV1B-S)") (class "Default")
      (node (ref "R10") (pin "1") (pinfunction "1_1") (pintype "passive"))
      (node (ref "SV1") (pin "10") (pinfunction "S_10") (pintype "passive"))
    )
    (net (code "86") (name "Net-(SV1C-S)") (class "Default")
      (node (ref "R11") (pin "1") (pinfunction "1_1") (pintype "passive"))
      (node (ref "SV1") (pin "11") (pinfunction "S_11") (pintype "passive"))
    )
    (net (code "87") (name "Net-(SV1D-S)") (class "Default")
      (node (ref "R12") (pin "1") (pinfunction "1_1") (pintype "passive"))
      (node (ref "SV1") (pin "12") (pinfunction "S_12") (pintype "passive"))
    )
    (net (code "88") (name "Net-(SV1E-S)") (class "Default")
      (node (ref "R13") (pin "1") (pinfunction "1_1") (pintype "passive"))
      (node (ref "SV1") (pin "13") (pinfunction "S_13") (pintype "passive"))
    )
    (net (code "89") (name "Net-(SV1F-S)") (class "Default")
      (node (ref "R14") (pin "1") (pinfunction "1_1") (pintype "passive"))
      (node (ref "SV1") (pin "14") (pinfunction "S_14") (pintype "passive"))
    )
    (net (code "90") (name "Net-(SV1G-S)") (class "Default")
      (node (ref "R15") (pin "1") (pinfunction "1_1") (pintype "passive"))
      (node (ref "SV1") (pin "15") (pinfunction "S_15") (pintype "passive"))
    )
    (net (code "91") (name "Net-(SV1H-S)") (class "Default")
      (node (ref "R16") (pin "1") (pinfunction "1_1") (pintype "passive"))
      (node (ref "SV1") (pin "16") (pinfunction "S_16") (pintype "passive"))
    )
    (net (code "92") (name "Net-(SV1L-S)") (class "Default")
      (node (ref "R2") (pin "1") (pinfunction "1_1") (pintype "passive"))
      (node (ref "SV1") (pin "2") (pinfunction "S_2") (pintype "passive"))
    )
    (net (code "93") (name "Net-(SV1N-S)") (class "Default")
      (node (ref "R3") (pin "1") (pinfunction "1_1") (pintype "passive"))
      (node (ref "SV1") (pin "3") (pinfunction "S_3") (pintype "passive"))
    )
    (net (code "94") (name "Net-(SV1O-S)") (class "Default")
      (node (ref "R4") (pin "1") (pinfunction "1_1") (pintype "passive"))
      (node (ref "SV1") (pin "4") (pinfunction "S_4") (pintype "passive"))
    )
    (net (code "95") (name "Net-(SV1P-S)") (class "Default")
      (node (ref "R5") (pin "1") (pinfunction "1_1") (pintype "passive"))
      (node (ref "SV1") (pin "5") (pinfunction "S_5") (pintype "passive"))
    )
    (net (code "96") (name "Net-(SV1Q-S)") (class "Default")
      (node (ref "R6") (pin "1") (pinfunction "1_1") (pintype "passive"))
      (node (ref "SV1") (pin "6") (pinfunction "S_6") (pintype "passive"))
    )
    (net (code "97") (name "Net-(SV1R-S)") (class "Default")
      (node (ref "R7") (pin "1") (pinfunction "1_1") (pintype "passive"))
      (node (ref "SV1") (pin "7") (pinfunction "S_7") (pintype "passive"))
    )
    (net (code "98") (name "Net-(SV1S-S)") (class "Default")
      (node (ref "R8") (pin "1") (pinfunction "1_1") (pintype "passive"))
      (node (ref "SV1") (pin "8") (pinfunction "S_8") (pintype "passive"))
    )
    (net (code "99") (name "Net-(SV1T-S)") (class "Default")
      (node (ref "R9") (pin "1") (pinfunction "1_1") (pintype "passive"))
      (node (ref "SV1") (pin "9") (pinfunction "S_9") (pintype "passive"))
    )
  )
)
